# LED20-A1-P02.net
KiCad netlist of a schematic drawn in Altium Designer
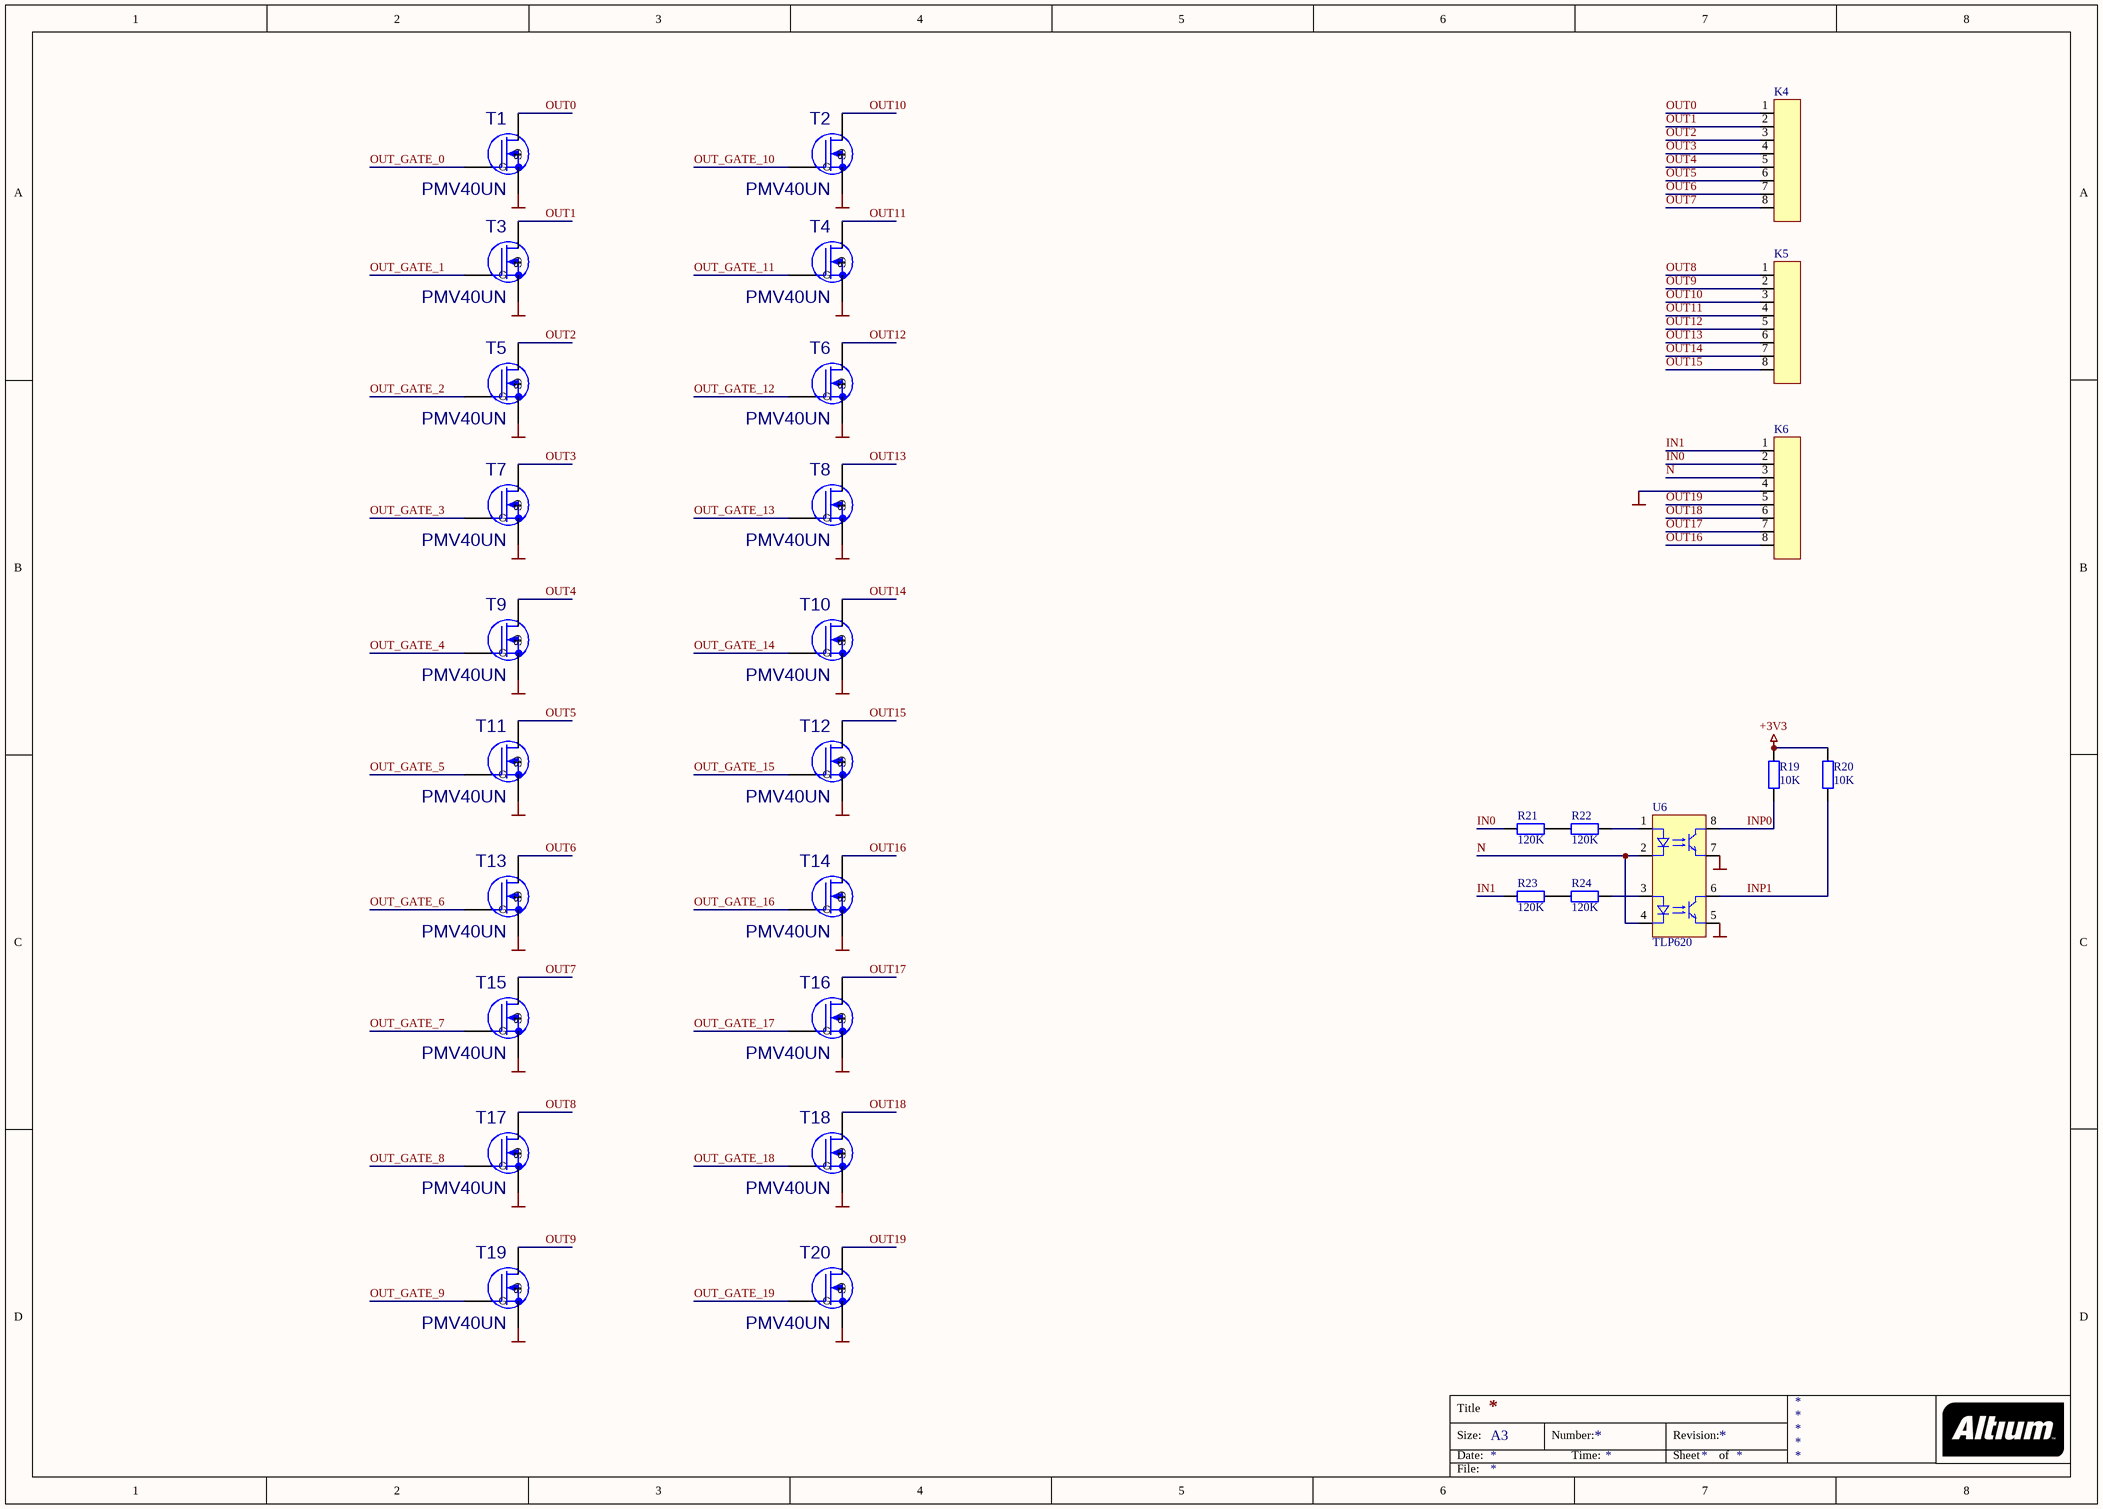
[diagram p0: LED20-A1-P02.SchDoc]

(export (version "E")
  (design (tool "Eeschema 10.0.6"))
  (components
    (comp (ref "K4")
      (value "Terminal Block Connector, 3.81mm, Right Angle")
      (footprint "CONN_3.81_8")
      (description "Terminal Block Connector, 3.81mm, 8pin")
      (libsource (lib "fractal_lib") (part "CONN_TB_3.81_8PIN"))
    )
    (comp (ref "K5")
      (value "Terminal Block Connector, 3.81mm, Right Angle")
      (footprint "CONN_3.81_8")
      (description "Terminal Block Connector, 3.81mm, 8pin")
      (libsource (lib "fractal_lib") (part "CONN_TB_3.81_8PIN"))
    )
    (comp (ref "K6")
      (value "Terminal Block Connector, 3.81mm, Right Angle")
      (footprint "CONN_3.81_8")
      (description "Terminal Block Connector, 3.81mm, 8pin")
      (libsource (lib "fractal_lib") (part "CONN_TB_3.81_8PIN"))
    )
    (comp (ref "R19")
      (value "10K")
      (footprint "RC0805-1")
      (description "Chip Resistor 0805")
      (libsource (lib "Resistors") (part "RES0805"))
    )
    (comp (ref "R20")
      (value "10K")
      (footprint "RC0805-1")
      (description "Chip Resistor 0805")
      (libsource (lib "Resistors") (part "RES0805"))
    )
    (comp (ref "R21")
      (value "120K")
      (footprint "RC1206-1")
      (description "Chip Resistor 1206")
      (libsource (lib "Resistors") (part "RES1206"))
    )
    (comp (ref "R22")
      (value "120K")
      (footprint "RC1206-1")
      (description "Chip Resistor 1206")
      (libsource (lib "Resistors") (part "RES1206"))
    )
    (comp (ref "R23")
      (value "120K")
      (footprint "RC1206-1")
      (description "Chip Resistor 1206")
      (libsource (lib "Resistors") (part "RES1206"))
    )
    (comp (ref "R24")
      (value "120K")
      (footprint "RC1206-1")
      (description "Chip Resistor 1206")
      (libsource (lib "Resistors") (part "RES1206"))
    )
    (comp (ref "T1") (value "PMV40UN") (footprint "SOT-23") (libsource (lib "ALINEA") (part "PMV40UN")))
    (comp (ref "T2") (value "PMV40UN") (footprint "SOT-23") (libsource (lib "ALINEA") (part "PMV40UN")))
    (comp (ref "T3") (value "PMV40UN") (footprint "SOT-23") (libsource (lib "ALINEA") (part "PMV40UN")))
    (comp (ref "T4") (value "PMV40UN") (footprint "SOT-23") (libsource (lib "ALINEA") (part "PMV40UN")))
    (comp (ref "T5") (value "PMV40UN") (footprint "SOT-23") (libsource (lib "ALINEA") (part "PMV40UN")))
    (comp (ref "T6") (value "PMV40UN") (footprint "SOT-23") (libsource (lib "ALINEA") (part "PMV40UN")))
    (comp (ref "T7") (value "PMV40UN") (footprint "SOT-23") (libsource (lib "ALINEA") (part "PMV40UN")))
    (comp (ref "T8") (value "PMV40UN") (footprint "SOT-23") (libsource (lib "ALINEA") (part "PMV40UN")))
    (comp (ref "T9") (value "PMV40UN") (footprint "SOT-23") (libsource (lib "ALINEA") (part "PMV40UN")))
    (comp (ref "T10") (value "PMV40UN") (footprint "SOT-23") (libsource (lib "ALINEA") (part "PMV40UN")))
    (comp (ref "T11") (value "PMV40UN") (footprint "SOT-23") (libsource (lib "ALINEA") (part "PMV40UN")))
    (comp (ref "T12") (value "PMV40UN") (footprint "SOT-23") (libsource (lib "ALINEA") (part "PMV40UN")))
    (comp (ref "T13") (value "PMV40UN") (footprint "SOT-23") (libsource (lib "ALINEA") (part "PMV40UN")))
    (comp (ref "T14") (value "PMV40UN") (footprint "SOT-23") (libsource (lib "ALINEA") (part "PMV40UN")))
    (comp (ref "T15") (value "PMV40UN") (footprint "SOT-23") (libsource (lib "ALINEA") (part "PMV40UN")))
    (comp (ref "T16") (value "PMV40UN") (footprint "SOT-23") (libsource (lib "ALINEA") (part "PMV40UN")))
    (comp (ref "T17") (value "PMV40UN") (footprint "SOT-23") (libsource (lib "ALINEA") (part "PMV40UN")))
    (comp (ref "T18") (value "PMV40UN") (footprint "SOT-23") (libsource (lib "ALINEA") (part "PMV40UN")))
    (comp (ref "T19") (value "PMV40UN") (footprint "SOT-23") (libsource (lib "ALINEA") (part "PMV40UN")))
    (comp (ref "T20") (value "PMV40UN") (footprint "SOT-23") (libsource (lib "ALINEA") (part "PMV40UN")))
    (comp (ref "U6")
      (value "TLP620")
      (footprint "DIP8")
      (description "digital temperature sensor")
      (libsource (lib "fractal_lib") (part "TLP620"))
    )
  )
  (nets
    (net (code "1") (name "+3V3") (class "Default")
      (node (ref "R19") (pin "1") (pinfunction "1_1") (pintype "passive"))
      (node (ref "R20") (pin "1") (pinfunction "1_1") (pintype "passive"))
    )
    (net (code "2") (name "/IN0") (class "Default")
      (node (ref "K6") (pin "2") (pinfunction "K_2") (pintype "passive"))
      (node (ref "R21") (pin "1") (pinfunction "1_1") (pintype "passive"))
    )
    (net (code "3") (name "/IN1") (class "Default")
      (node (ref "K6") (pin "1") (pinfunction "A_1") (pintype "passive"))
      (node (ref "R23") (pin "1") (pinfunction "1_1") (pintype "passive"))
    )
    (net (code "4") (name "/INP0") (class "Default")
      (node (ref "R19") (pin "2") (pinfunction "2_2") (pintype "passive"))
      (node (ref "U6") (pin "8") (pinfunction "C_8") (pintype "passive"))
    )
    (net (code "5") (name "/INP1") (class "Default")
      (node (ref "R20") (pin "2") (pinfunction "2_2") (pintype "passive"))
      (node (ref "U6") (pin "6") (pinfunction "C_6") (pintype "passive"))
    )
    (net (code "6") (name "/N") (class "Default")
      (node (ref "K6") (pin "3") (pinfunction "A_3") (pintype "passive"))
      (node (ref "U6") (pin "2") (pinfunction "K_2") (pintype "passive"))
      (node (ref "U6") (pin "4") (pinfunction "K_4") (pintype "passive"))
    )
    (net (code "7") (name "/OUT0") (class "Default")
      (node (ref "K4") (pin "1") (pinfunction "A_1") (pintype "passive"))
      (node (ref "T1") (pin "3") (pinfunction "D_3") (pintype "passive"))
    )
    (net (code "8") (name "/OUT1") (class "Default")
      (node (ref "K4") (pin "2") (pinfunction "K_2") (pintype "passive"))
      (node (ref "T3") (pin "3") (pinfunction "D_3") (pintype "passive"))
    )
    (net (code "9") (name "/OUT2") (class "Default")
      (node (ref "K4") (pin "3") (pinfunction "A_3") (pintype "passive"))
      (node (ref "T5") (pin "3") (pinfunction "D_3") (pintype "passive"))
    )
    (net (code "10") (name "/OUT3") (class "Default")
      (node (ref "K4") (pin "4") (pinfunction "K_4") (pintype "passive"))
      (node (ref "T7") (pin "3") (pinfunction "D_3") (pintype "passive"))
    )
    (net (code "11") (name "/OUT4") (class "Default")
      (node (ref "K4") (pin "5") (pinfunction "E_5") (pintype "passive"))
      (node (ref "T9") (pin "3") (pinfunction "D_3") (pintype "passive"))
    )
    (net (code "12") (name "/OUT5") (class "Default")
      (node (ref "K4") (pin "6") (pinfunction "C_6") (pintype "passive"))
      (node (ref "T11") (pin "3") (pinfunction "D_3") (pintype "passive"))
    )
    (net (code "13") (name "/OUT6") (class "Default")
      (node (ref "K4") (pin "7") (pinfunction "E_7") (pintype "passive"))
      (node (ref "T13") (pin "3") (pinfunction "D_3") (pintype "passive"))
    )
    (net (code "14") (name "/OUT7") (class "Default")
      (node (ref "K4") (pin "8") (pinfunction "C_8") (pintype "passive"))
      (node (ref "T15") (pin "3") (pinfunction "D_3") (pintype "passive"))
    )
    (net (code "15") (name "/OUT8") (class "Default")
      (node (ref "K5") (pin "1") (pinfunction "A_1") (pintype "passive"))
      (node (ref "T17") (pin "3") (pinfunction "D_3") (pintype "passive"))
    )
    (net (code "16") (name "/OUT9") (class "Default")
      (node (ref "K5") (pin "2") (pinfunction "K_2") (pintype "passive"))
      (node (ref "T19") (pin "3") (pinfunction "D_3") (pintype "passive"))
    )
    (net (code "17") (name "/OUT10") (class "Default")
      (node (ref "K5") (pin "3") (pinfunction "A_3") (pintype "passive"))
      (node (ref "T2") (pin "3") (pinfunction "D_3") (pintype "passive"))
    )
    (net (code "18") (name "/OUT11") (class "Default")
      (node (ref "K5") (pin "4") (pinfunction "K_4") (pintype "passive"))
      (node (ref "T4") (pin "3") (pinfunction "D_3") (pintype "passive"))
    )
    (net (code "19") (name "/OUT12") (class "Default")
      (node (ref "K5") (pin "5") (pinfunction "E_5") (pintype "passive"))
      (node (ref "T6") (pin "3") (pinfunction "D_3") (pintype "passive"))
    )
    (net (code "20") (name "/OUT13") (class "Default")
      (node (ref "K5") (pin "6") (pinfunction "C_6") (pintype "passive"))
      (node (ref "T8") (pin "3") (pinfunction "D_3") (pintype "passive"))
    )
    (net (code "21") (name "/OUT14") (class "Default")
      (node (ref "K5") (pin "7") (pinfunction "E_7") (pintype "passive"))
      (node (ref "T10") (pin "3") (pinfunction "D_3") (pintype "passive"))
    )
    (net (code "22") (name "/OUT15") (class "Default")
      (node (ref "K5") (pin "8") (pinfunction "C_8") (pintype "passive"))
      (node (ref "T12") (pin "3") (pinfunction "D_3") (pintype "passive"))
    )
    (net (code "23") (name "/OUT16") (class "Default")
      (node (ref "K6") (pin "8") (pinfunction "C_8") (pintype "passive"))
      (node (ref "T14") (pin "3") (pinfunction "D_3") (pintype "passive"))
    )
    (net (code "24") (name "/OUT17") (class "Default")
      (node (ref "K6") (pin "7") (pinfunction "E_7") (pintype "passive"))
      (node (ref "T16") (pin "3") (pinfunction "D_3") (pintype "passive"))
    )
    (net (code "25") (name "/OUT18") (class "Default")
      (node (ref "K6") (pin "6") (pinfunction "C_6") (pintype "passive"))
      (node (ref "T18") (pin "3") (pinfunction "D_3") (pintype "passive"))
    )
    (net (code "26") (name "/OUT19") (class "Default")
      (node (ref "K6") (pin "5") (pinfunction "E_5") (pintype "passive"))
      (node (ref "T20") (pin "3") (pinfunction "D_3") (pintype "passive"))
    )
    (net (code "27") (name "/OUT_GATE_0") (class "Default")
      (node (ref "T1") (pin "1") (pinfunction "G_1") (pintype "passive"))
    )
    (net (code "28") (name "/OUT_GATE_1") (class "Default")
      (node (ref "T3") (pin "1") (pinfunction "G_1") (pintype "passive"))
    )
    (net (code "29") (name "/OUT_GATE_2") (class "Default")
      (node (ref "T5") (pin "1") (pinfunction "G_1") (pintype "passive"))
    )
    (net (code "30") (name "/OUT_GATE_3") (class "Default")
      (node (ref "T7") (pin "1") (pinfunction "G_1") (pintype "passive"))
    )
    (net (code "31") (name "/OUT_GATE_4") (class "Default")
      (node (ref "T9") (pin "1") (pinfunction "G_1") (pintype "passive"))
    )
    (net (code "32") (name "/OUT_GATE_5") (class "Default")
      (node (ref "T11") (pin "1") (pinfunction "G_1") (pintype "passive"))
    )
    (net (code "33") (name "/OUT_GATE_6") (class "Default")
      (node (ref "T13") (pin "1") (pinfunction "G_1") (pintype "passive"))
    )
    (net (code "34") (name "/OUT_GATE_7") (class "Default")
      (node (ref "T15") (pin "1") (pinfunction "G_1") (pintype "passive"))
    )
    (net (code "35") (name "/OUT_GATE_8") (class "Default")
      (node (ref "T17") (pin "1") (pinfunction "G_1") (pintype "passive"))
    )
    (net (code "36") (name "/OUT_GATE_9") (class "Default")
      (node (ref "T19") (pin "1") (pinfunction "G_1") (pintype "passive"))
    )
    (net (code "37") (name "/OUT_GATE_10") (class "Default")
      (node (ref "T2") (pin "1") (pinfunction "G_1") (pintype "passive"))
    )
    (net (code "38") (name "/OUT_GATE_11") (class "Default")
      (node (ref "T4") (pin "1") (pinfunction "G_1") (pintype "passive"))
    )
    (net (code "39") (name "/OUT_GATE_12") (class "Default")
      (node (ref "T6") (pin "1") (pinfunction "G_1") (pintype "passive"))
    )
    (net (code "40") (name "/OUT_GATE_13") (class "Default")
      (node (ref "T8") (pin "1") (pinfunction "G_1") (pintype "passive"))
    )
    (net (code "41") (name "/OUT_GATE_14") (class "Default")
      (node (ref "T10") (pin "1") (pinfunction "G_1") (pintype "passive"))
    )
    (net (code "42") (name "/OUT_GATE_15") (class "Default")
      (node (ref "T12") (pin "1") (pinfunction "G_1") (pintype "passive"))
    )
    (net (code "43") (name "/OUT_GATE_16") (class "Default")
      (node (ref "T14") (pin "1") (pinfunction "G_1") (pintype "passive"))
    )
    (net (code "44") (name "/OUT_GATE_17") (class "Default")
      (node (ref "T16") (pin "1") (pinfunction "G_1") (pintype "passive"))
    )
    (net (code "45") (name "/OUT_GATE_18") (class "Default")
      (node (ref "T18") (pin "1") (pinfunction "G_1") (pintype "passive"))
    )
    (net (code "46") (name "/OUT_GATE_19") (class "Default")
      (node (ref "T20") (pin "1") (pinfunction "G_1") (pintype "passive"))
    )
    (net (code "47") (name "GND") (class "Default")
      (node (ref "K6") (pin "4") (pinfunction "K_4") (pintype "passive"))
      (node (ref "T1") (pin "2") (pinfunction "S_2") (pintype "passive"))
      (node (ref "T10") (pin "2") (pinfunction "S_2") (pintype "passive"))
      (node (ref "T11") (pin "2") (pinfunction "S_2") (pintype "passive"))
      (node (ref "T12") (pin "2") (pinfunction "S_2") (pintype "passive"))
      (node (ref "T13") (pin "2") (pinfunction "S_2") (pintype "passive"))
      (node (ref "T14") (pin "2") (pinfunction "S_2") (pintype "passive"))
      (node (ref "T15") (pin "2") (pinfunction "S_2") (pintype "passive"))
      (node (ref "T16") (pin "2") (pinfunction "S_2") (pintype "passive"))
      (node (ref "T17") (pin "2") (pinfunction "S_2") (pintype "passive"))
      (node (ref "T18") (pin "2") (pinfunction "S_2") (pintype "passive"))
      (node (ref "T19") (pin "2") (pinfunction "S_2") (pintype "passive"))
      (node (ref "T2") (pin "2") (pinfunction "S_2") (pintype "passive"))
      (node (ref "T20") (pin "2") (pinfunction "S_2") (pintype "passive"))
      (node (ref "T3") (pin "2") (pinfunction "S_2") (pintype "passive"))
      (node (ref "T4") (pin "2") (pinfunction "S_2") (pintype "passive"))
      (node (ref "T5") (pin "2") (pinfunction "S_2") (pintype "passive"))
      (node (ref "T6") (pin "2") (pinfunction "S_2") (pintype "passive"))
      (node (ref "T7") (pin "2") (pinfunction "S_2") (pintype "passive"))
      (node (ref "T8") (pin "2") (pinfunction "S_2") (pintype "passive"))
      (node (ref "T9") (pin "2") (pinfunction "S_2") (pintype "passive"))
      (node (ref "U6") (pin "5") (pinfunction "E_5") (pintype "passive"))
      (node (ref "U6") (pin "7") (pinfunction "E_7") (pintype "passive"))
    )
    (net (code "48") (name "Net-(R21-Pad2)") (class "Default")
      (node (ref "R21") (pin "2") (pinfunction "2_2") (pintype "passive"))
      (node (ref "R22") (pin "1") (pinfunction "1_1") (pintype "passive"))
    )
    (net (code "49") (name "Net-(R22-Pad2)") (class "Default")
      (node (ref "R22") (pin "2") (pinfunction "2_2") (pintype "passive"))
      (node (ref "U6") (pin "1") (pinfunction "A_1") (pintype "passive"))
    )
    (net (code "50") (name "Net-(R23-Pad2)") (class "Default")
      (node (ref "R23") (pin "2") (pinfunction "2_2") (pintype "passive"))
      (node (ref "R24") (pin "1") (pinfunction "1_1") (pintype "passive"))
    )
    (net (code "51") (name "Net-(R24-Pad2)") (class "Default")
      (node (ref "R24") (pin "2") (pinfunction "2_2") (pintype "passive"))
      (node (ref "U6") (pin "3") (pinfunction "A_3") (pintype "passive"))
    )
  )
)
